# INA169.net
KiCad netlist of a schematic drawn in Altium Designer
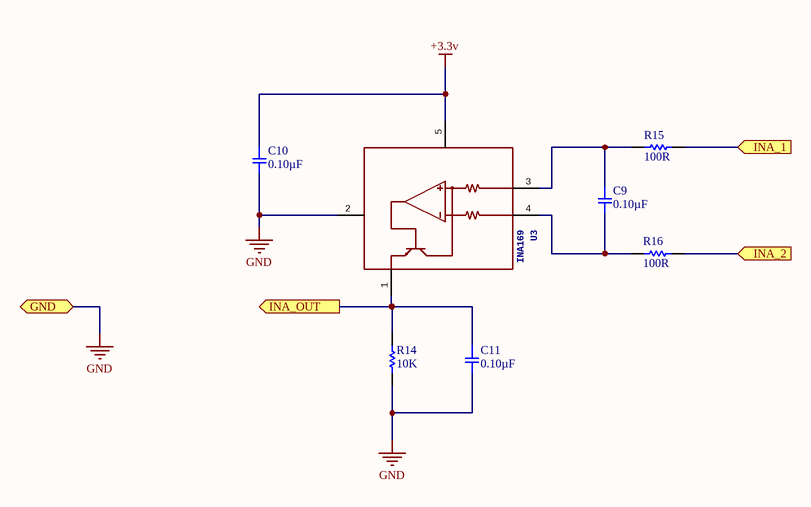
[diagram p0: INA169.SchDoc]

(export (version "E")
  (design (tool "Eeschema 10.0.6"))
  (components
    (comp (ref "C9")
      (value "0.10µF")
      (footprint "SMD-0603C")
      (description "CAP CER 0.1UF 16V X7R 0603")
      (fields
        (field (name "DIGI-KEY PART NUMBER") "490-5796-1-ND")
        (field (name "PART NUMBER") "GCJ188R71C104KA01D")
      )
      (libsource (lib "capacitor_murata_0603") (part "GCJ188R71C104KA01D"))
    )
    (comp (ref "C10")
      (value "0.10µF")
      (footprint "SMD-0603C")
      (description "CAP CER 0.1UF 16V X7R 0603")
      (fields
        (field (name "DIGI-KEY PART NUMBER") "490-5796-1-ND")
        (field (name "PART NUMBER") "GCJ188R71C104KA01D")
      )
      (libsource (lib "capacitor_murata_0603") (part "GCJ188R71C104KA01D"))
    )
    (comp (ref "C11")
      (value "0.10µF")
      (footprint "SMD-0603C")
      (description "CAP CER 0.1UF 16V X7R 0603")
      (fields
        (field (name "DIGI-KEY PART NUMBER") "490-5796-1-ND")
        (field (name "PART NUMBER") "GCJ188R71C104KA01D")
      )
      (libsource (lib "capacitor_murata_0603") (part "GCJ188R71C104KA01D"))
    )
    (comp (ref "R14")
      (value "10K")
      (footprint "SMD-0603-RES")
      (description "RES SMD 10K OHM 5% 1/16W 0402")
      (fields (field (name "Comment") "RC0402JR-071KL"))
      (libsource (lib "Schlib1") (part "RES 1K 0402"))
    )
    (comp (ref "R15")
      (value "100R")
      (footprint "SMD-0603-RES")
      (description "RES SMD 10K OHM 5% 1/16W 0402")
      (fields (field (name "Comment") "RC0402JR-071KL"))
      (libsource (lib "Schlib1") (part "RES 1K 0402"))
    )
    (comp (ref "R16")
      (value "100R")
      (footprint "SMD-0603-RES")
      (description "RES SMD 10K OHM 5% 1/16W 0402")
      (fields (field (name "Comment") "RC0402JR-071KL"))
      (libsource (lib "Schlib1") (part "RES 1K 0402"))
    )
    (comp (ref "U3")
      (value "INA169")
      (footprint "SOT23-5")
      (fields (field (name "MF") "Texas Instruments"))
      (libsource (lib "INA169") (part "INA169"))
    )
  )
  (nets
    (net (code "1") (name "+3.3v") (class "Default")
      (node (ref "C10") (pin "1") (pinfunction "1_1") (pintype "passive"))
      (node (ref "U3") (pin "5") (pinfunction "V+_5") (pintype "passive"))
    )
    (net (code "2") (name "/INA_1") (class "Default")
      (node (ref "R15") (pin "1") (pinfunction "1_1") (pintype "passive"))
    )
    (net (code "3") (name "/INA_2") (class "Default")
      (node (ref "R16") (pin "1") (pinfunction "1_1") (pintype "passive"))
    )
    (net (code "4") (name "/INA_OUT") (class "Default")
      (node (ref "C11") (pin "1") (pinfunction "1_1") (pintype "passive"))
      (node (ref "R14") (pin "2") (pinfunction "2_2") (pintype "passive"))
      (node (ref "U3") (pin "1") (pinfunction "OUT_1") (pintype "passive"))
    )
    (net (code "5") (name "GND") (class "Default")
      (node (ref "C10") (pin "2") (pinfunction "2_2") (pintype "passive"))
      (node (ref "C11") (pin "2") (pinfunction "2_2") (pintype "passive"))
      (node (ref "R14") (pin "1") (pinfunction "1_1") (pintype "passive"))
      (node (ref "U3") (pin "2") (pinfunction "GND_2") (pintype "passive"))
    )
    (net (code "6") (name "Net-(U3-VIN+)") (class "Default")
      (node (ref "C9") (pin "1") (pinfunction "1_1") (pintype "passive"))
      (node (ref "R15") (pin "2") (pinfunction "2_2") (pintype "passive"))
      (node (ref "U3") (pin "3") (pinfunction "VIN+_3") (pintype "passive"))
    )
    (net (code "7") (name "Net-(U3-VIN-)") (class "Default")
      (node (ref "C9") (pin "2") (pinfunction "2_2") (pintype "passive"))
      (node (ref "R16") (pin "2") (pinfunction "2_2") (pintype "passive"))
      (node (ref "U3") (pin "4") (pinfunction "VIN-_4") (pintype "passive"))
    )
  )
)
